# E-P-099-R3_0.net
KiCad netlist of a schematic drawn in EAGLE
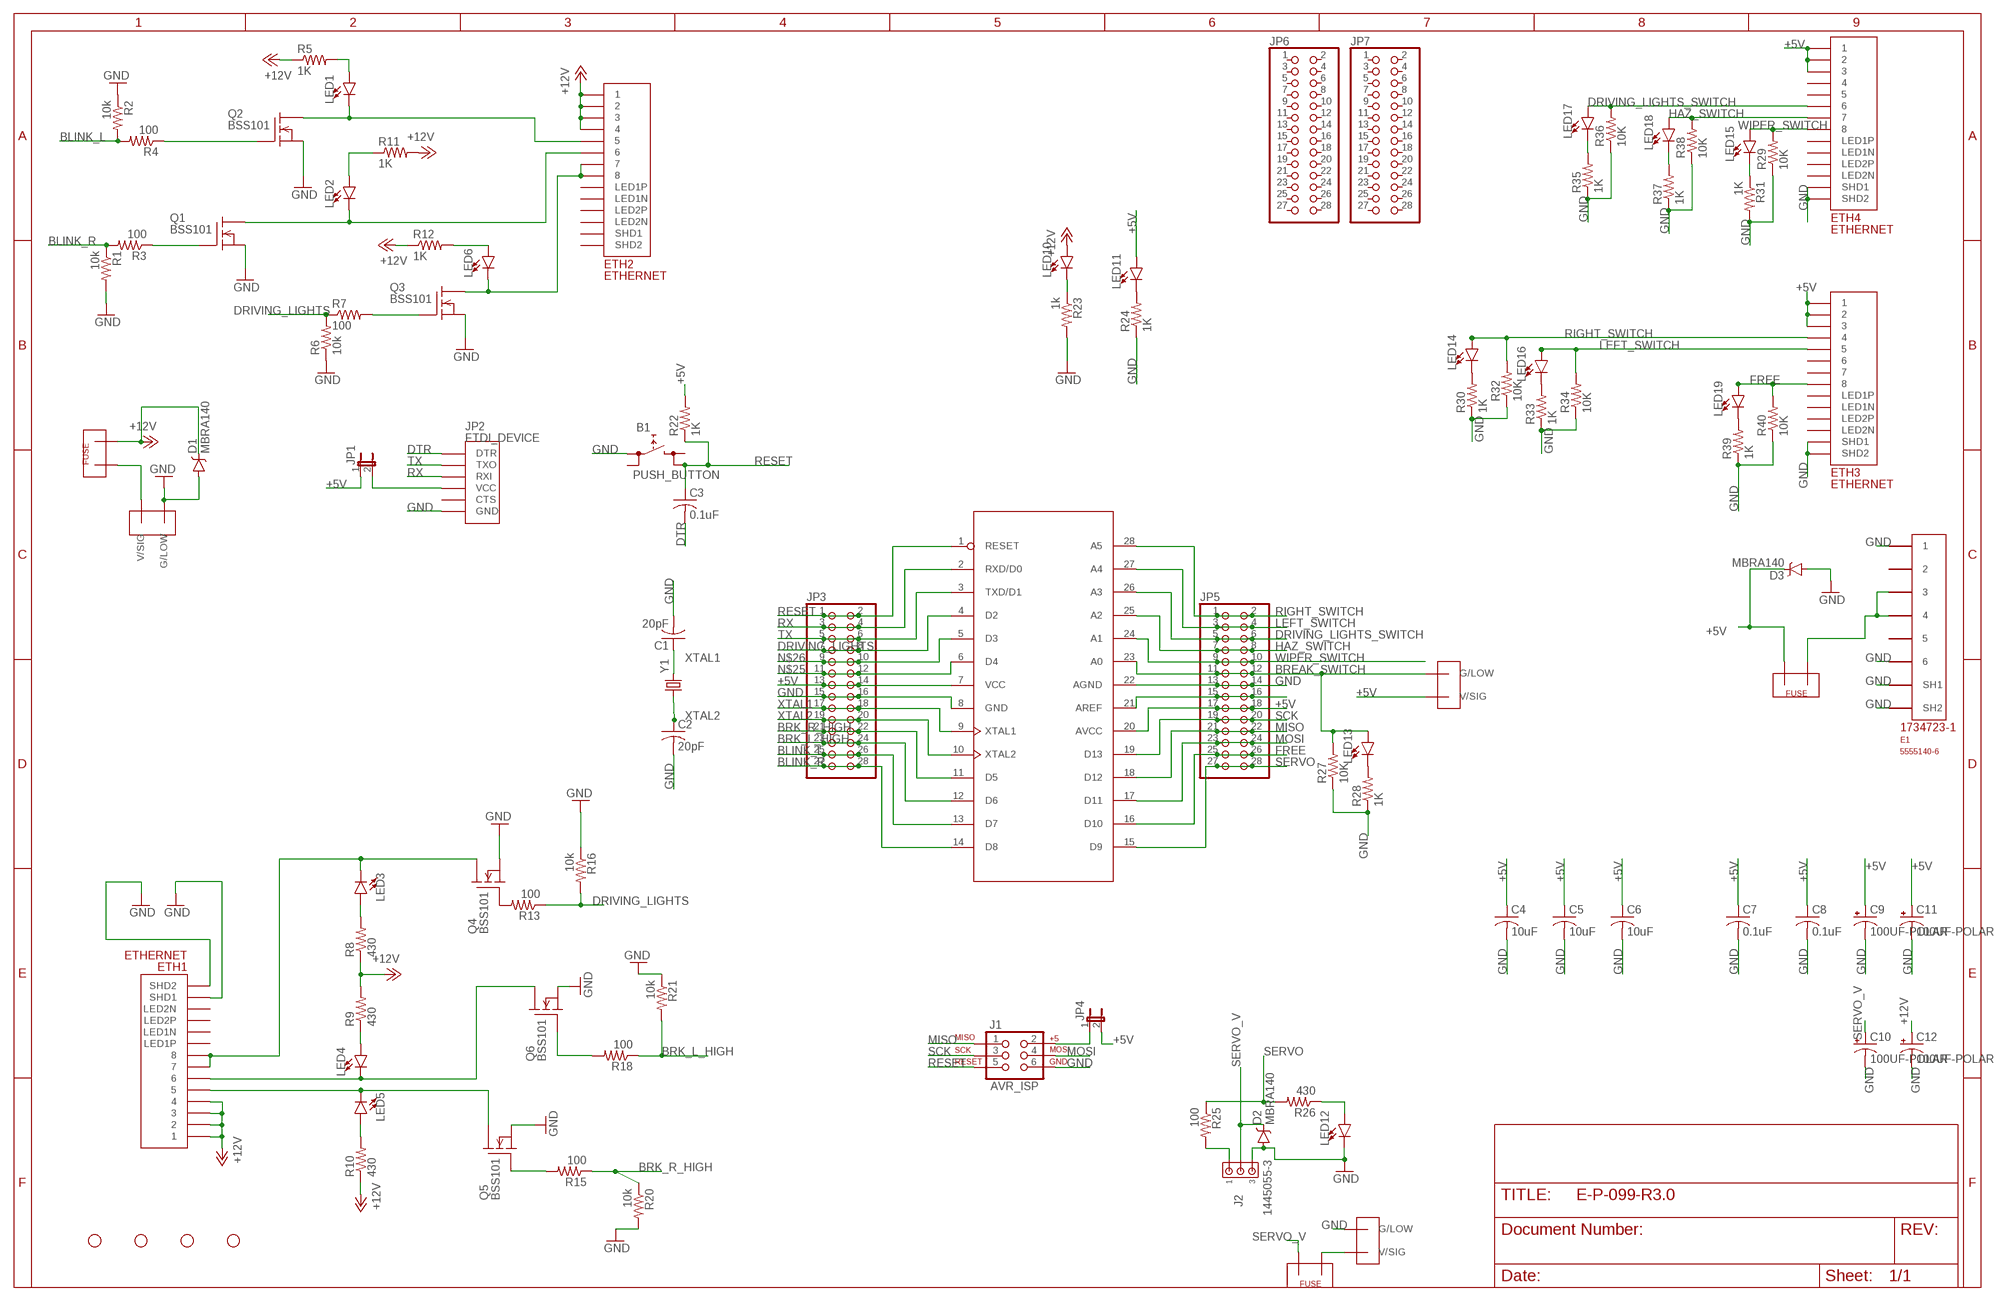
[diagram p0: schematic, sheet 1]

(export (version "E")
  (design (tool "Eeschema 10.0.6"))
  (components
    (comp (ref "AT1")
      (value "ATMEGA328")
      (footprint "eagle-import:DIP28-0.3IN")
      (libsource (lib "eagle-import") (part "ATMEGA328"))
    )
    (comp (ref "B1")
      (value "PUSH_BUTTON")
      (footprint "eagle-import:PUSHBUTTON")
      (libsource (lib "eagle-import") (part "PUSH_BUTTON"))
    )
    (comp (ref "C1")
      (value "20pF")
      (footprint "eagle-import:C0805")
      (libsource (lib "eagle-import") (part "C-USC0805"))
    )
    (comp (ref "C2")
      (value "20pF")
      (footprint "eagle-import:C0805")
      (libsource (lib "eagle-import") (part "C-USC0805"))
    )
    (comp (ref "C3")
      (value "0.1uF")
      (footprint "eagle-import:C0805")
      (libsource (lib "eagle-import") (part "C-USC0805"))
    )
    (comp (ref "C4")
      (value "10uF")
      (footprint "eagle-import:C0805")
      (libsource (lib "eagle-import") (part "C-USC0805"))
    )
    (comp (ref "C5")
      (value "10uF")
      (footprint "eagle-import:C0805")
      (libsource (lib "eagle-import") (part "C-USC0805"))
    )
    (comp (ref "C6")
      (value "10uF")
      (footprint "eagle-import:C0805")
      (libsource (lib "eagle-import") (part "C-USC0805"))
    )
    (comp (ref "C7")
      (value "0.1uF")
      (footprint "eagle-import:C0805")
      (libsource (lib "eagle-import") (part "C-USC0805"))
    )
    (comp (ref "C8")
      (value "0.1uF")
      (footprint "eagle-import:C0805")
      (libsource (lib "eagle-import") (part "C-USC0805"))
    )
    (comp (ref "C9")
      (value "100UF-POLAR")
      (footprint "eagle-import:EEU-FR1H101")
      (libsource (lib "eagle-import") (part "100UF-POLAR"))
    )
    (comp (ref "C10")
      (value "100UF-POLAR")
      (footprint "eagle-import:EEU-FR1H101")
      (libsource (lib "eagle-import") (part "100UF-POLAR"))
    )
    (comp (ref "C11")
      (value "100UF-POLAR")
      (footprint "eagle-import:EEU-FR1H101")
      (libsource (lib "eagle-import") (part "100UF-POLAR"))
    )
    (comp (ref "C12")
      (value "100UF-POLAR")
      (footprint "eagle-import:EEU-FR1H101")
      (libsource (lib "eagle-import") (part "100UF-POLAR"))
    )
    (comp (ref "D1")
      (value "MBRA140")
      (footprint "eagle-import:SMA-DIODE")
      (libsource (lib "eagle-import") (part "MBRA140"))
    )
    (comp (ref "D2")
      (value "MBRA140")
      (footprint "eagle-import:SMA-DIODE")
      (libsource (lib "eagle-import") (part "MBRA140"))
    )
    (comp (ref "D3")
      (value "MBRA140")
      (footprint "eagle-import:SMA-DIODE")
      (libsource (lib "eagle-import") (part "MBRA140"))
    )
    (comp (ref "E1")
      (value "5555140-6")
      (footprint "eagle-import:1734723-1_RJ11")
      (libsource (lib "eagle-import") (part "5555140-6"))
    )
    (comp (ref "ETH1")
      (value "ETHERNET")
      (footprint "eagle-import:A122645-ND")
      (libsource (lib "eagle-import") (part "ETHERNET"))
    )
    (comp (ref "ETH2")
      (value "ETHERNET")
      (footprint "eagle-import:A122645-ND")
      (libsource (lib "eagle-import") (part "ETHERNET"))
    )
    (comp (ref "ETH3")
      (value "ETHERNET")
      (footprint "eagle-import:A122645-ND")
      (libsource (lib "eagle-import") (part "ETHERNET"))
    )
    (comp (ref "ETH4")
      (value "ETHERNET")
      (footprint "eagle-import:A122645-ND")
      (libsource (lib "eagle-import") (part "ETHERNET"))
    )
    (comp (ref "F1")
      (value "FUSEMINI-BLADE")
      (footprint "eagle-import:MINI-BLADE-FUSE")
      (libsource (lib "eagle-import") (part "FUSEMINI-BLADE"))
    )
    (comp (ref "F2")
      (value "FUSEMINI-BLADE")
      (footprint "eagle-import:MINI-BLADE-FUSE")
      (libsource (lib "eagle-import") (part "FUSEMINI-BLADE"))
    )
    (comp (ref "F3")
      (value "FUSEMINI-BLADE")
      (footprint "eagle-import:MINI-BLADE-FUSE")
      (libsource (lib "eagle-import") (part "FUSEMINI-BLADE"))
    )
    (comp (ref "J1")
      (value "AVR_ISP")
      (footprint "eagle-import:2X3")
      (libsource (lib "eagle-import") (part "AVR_SPI_PRG_6PTH"))
    )
    (comp (ref "J2")
      (value "1445055-3")
      (footprint "eagle-import:1445055-3")
      (libsource (lib "eagle-import") (part "1445055-3"))
    )
    (comp (ref "JP1")
      (value "JP1E")
      (footprint "eagle-import:JP1")
      (libsource (lib "eagle-import") (part "JP1E"))
    )
    (comp (ref "JP2")
      (value "FTDI_DEVICE")
      (footprint "eagle-import:FTDI_DEVICE_SIDE")
      (libsource (lib "eagle-import") (part "FTDI_DEVICE"))
    )
    (comp (ref "JP3")
      (value "PINHD-2X14")
      (footprint "eagle-import:2X14")
      (libsource (lib "eagle-import") (part "PINHD-2X14"))
    )
    (comp (ref "JP4")
      (value "JP1E")
      (footprint "eagle-import:JP1")
      (libsource (lib "eagle-import") (part "JP1E"))
    )
    (comp (ref "JP5")
      (value "PINHD-2X14")
      (footprint "eagle-import:2X14")
      (libsource (lib "eagle-import") (part "PINHD-2X14"))
    )
    (comp (ref "JP6")
      (value "PINHD-2X14")
      (footprint "eagle-import:2X14")
      (libsource (lib "eagle-import") (part "PINHD-2X14"))
    )
    (comp (ref "JP7")
      (value "PINHD-2X14")
      (footprint "eagle-import:2X14")
      (libsource (lib "eagle-import") (part "PINHD-2X14"))
    )
    (comp (ref "LED1")
      (value "LED0603")
      (footprint "eagle-import:LED-0603")
      (libsource (lib "eagle-import") (part "LED0603"))
    )
    (comp (ref "LED2")
      (value "LED0603")
      (footprint "eagle-import:LED-0603")
      (libsource (lib "eagle-import") (part "LED0603"))
    )
    (comp (ref "LED3")
      (value "LED0603")
      (footprint "eagle-import:LED-0603")
      (libsource (lib "eagle-import") (part "LED0603"))
    )
    (comp (ref "LED4")
      (value "LED0603")
      (footprint "eagle-import:LED-0603")
      (libsource (lib "eagle-import") (part "LED0603"))
    )
    (comp (ref "LED5")
      (value "LED0603")
      (footprint "eagle-import:LED-0603")
      (libsource (lib "eagle-import") (part "LED0603"))
    )
    (comp (ref "LED6")
      (value "LED0603")
      (footprint "eagle-import:LED-0603")
      (libsource (lib "eagle-import") (part "LED0603"))
    )
    (comp (ref "LED10")
      (value "LED0603")
      (footprint "eagle-import:LED-0603")
      (libsource (lib "eagle-import") (part "LED0603"))
    )
    (comp (ref "LED11")
      (value "LED0603")
      (footprint "eagle-import:LED-0603")
      (libsource (lib "eagle-import") (part "LED0603"))
    )
    (comp (ref "LED12")
      (value "LED0603")
      (footprint "eagle-import:LED-0603")
      (libsource (lib "eagle-import") (part "LED0603"))
    )
    (comp (ref "LED13")
      (value "LED0603")
      (footprint "eagle-import:LED-0603")
      (libsource (lib "eagle-import") (part "LED0603"))
    )
    (comp (ref "LED14")
      (value "LED0603")
      (footprint "eagle-import:LED-0603")
      (libsource (lib "eagle-import") (part "LED0603"))
    )
    (comp (ref "LED15")
      (value "LED0603")
      (footprint "eagle-import:LED-0603")
      (libsource (lib "eagle-import") (part "LED0603"))
    )
    (comp (ref "LED16")
      (value "LED0603")
      (footprint "eagle-import:LED-0603")
      (libsource (lib "eagle-import") (part "LED0603"))
    )
    (comp (ref "LED17")
      (value "LED0603")
      (footprint "eagle-import:LED-0603")
      (libsource (lib "eagle-import") (part "LED0603"))
    )
    (comp (ref "LED18")
      (value "LED0603")
      (footprint "eagle-import:LED-0603")
      (libsource (lib "eagle-import") (part "LED0603"))
    )
    (comp (ref "LED19")
      (value "LED0603")
      (footprint "eagle-import:LED-0603")
      (libsource (lib "eagle-import") (part "LED0603"))
    )
    (comp (ref "Q1")
      (value "BSS101")
      (footprint "eagle-import:TO92")
      (libsource (lib "eagle-import") (part "BSS101"))
    )
    (comp (ref "Q2")
      (value "BSS101")
      (footprint "eagle-import:TO92")
      (libsource (lib "eagle-import") (part "BSS101"))
    )
    (comp (ref "Q3")
      (value "BSS101")
      (footprint "eagle-import:TO92")
      (libsource (lib "eagle-import") (part "BSS101"))
    )
    (comp (ref "Q4")
      (value "BSS101")
      (footprint "eagle-import:TO92")
      (libsource (lib "eagle-import") (part "BSS101"))
    )
    (comp (ref "Q5")
      (value "BSS101")
      (footprint "eagle-import:TO92")
      (libsource (lib "eagle-import") (part "BSS101"))
    )
    (comp (ref "Q6")
      (value "BSS101")
      (footprint "eagle-import:TO92")
      (libsource (lib "eagle-import") (part "BSS101"))
    )
    (comp (ref "R1")
      (value "10k")
      (footprint "eagle-import:0805")
      (libsource (lib "eagle-import") (part "RESISTOR0805-RES"))
    )
    (comp (ref "R2")
      (value "10k")
      (footprint "eagle-import:0805")
      (libsource (lib "eagle-import") (part "RESISTOR0805-RES"))
    )
    (comp (ref "R3")
      (value "100")
      (footprint "eagle-import:0805")
      (libsource (lib "eagle-import") (part "RESISTOR0805-RES"))
    )
    (comp (ref "R4")
      (value "100")
      (footprint "eagle-import:0805")
      (libsource (lib "eagle-import") (part "RESISTOR0805-RES"))
    )
    (comp (ref "R5")
      (value "1K")
      (footprint "eagle-import:0805")
      (libsource (lib "eagle-import") (part "RESISTOR0805-RES"))
    )
    (comp (ref "R6")
      (value "10k")
      (footprint "eagle-import:0805")
      (libsource (lib "eagle-import") (part "RESISTOR0805-RES"))
    )
    (comp (ref "R7")
      (value "100")
      (footprint "eagle-import:0805")
      (libsource (lib "eagle-import") (part "RESISTOR0805-RES"))
    )
    (comp (ref "R8")
      (value "430")
      (footprint "eagle-import:0805")
      (libsource (lib "eagle-import") (part "RESISTOR0805-RES"))
    )
    (comp (ref "R9")
      (value "430")
      (footprint "eagle-import:0805")
      (libsource (lib "eagle-import") (part "RESISTOR0805-RES"))
    )
    (comp (ref "R10")
      (value "430")
      (footprint "eagle-import:0805")
      (libsource (lib "eagle-import") (part "RESISTOR0805-RES"))
    )
    (comp (ref "R11")
      (value "1K")
      (footprint "eagle-import:0805")
      (libsource (lib "eagle-import") (part "RESISTOR0805-RES"))
    )
    (comp (ref "R12")
      (value "1K")
      (footprint "eagle-import:0805")
      (libsource (lib "eagle-import") (part "RESISTOR0805-RES"))
    )
    (comp (ref "R13")
      (value "100")
      (footprint "eagle-import:0805")
      (libsource (lib "eagle-import") (part "RESISTOR0805-RES"))
    )
    (comp (ref "R15")
      (value "100")
      (footprint "eagle-import:0805")
      (libsource (lib "eagle-import") (part "RESISTOR0805-RES"))
    )
    (comp (ref "R16")
      (value "10k")
      (footprint "eagle-import:0805")
      (libsource (lib "eagle-import") (part "RESISTOR0805-RES"))
    )
    (comp (ref "R18")
      (value "100")
      (footprint "eagle-import:0805")
      (libsource (lib "eagle-import") (part "RESISTOR0805-RES"))
    )
    (comp (ref "R20")
      (value "10k")
      (footprint "eagle-import:0805")
      (libsource (lib "eagle-import") (part "RESISTOR0805-RES"))
    )
    (comp (ref "R21")
      (value "10k")
      (footprint "eagle-import:0805")
      (libsource (lib "eagle-import") (part "RESISTOR0805-RES"))
    )
    (comp (ref "R22")
      (value "1K")
      (footprint "eagle-import:0805")
      (libsource (lib "eagle-import") (part "RESISTOR0805-RES"))
    )
    (comp (ref "R23")
      (value "1k")
      (footprint "eagle-import:0805")
      (libsource (lib "eagle-import") (part "RESISTOR0805-RES"))
    )
    (comp (ref "R24")
      (value "1K")
      (footprint "eagle-import:0805")
      (libsource (lib "eagle-import") (part "RESISTOR0805-RES"))
    )
    (comp (ref "R25")
      (value "100")
      (footprint "eagle-import:0805")
      (libsource (lib "eagle-import") (part "RESISTOR0805-RES"))
    )
    (comp (ref "R26")
      (value "430")
      (footprint "eagle-import:0805")
      (libsource (lib "eagle-import") (part "RESISTOR0805-RES"))
    )
    (comp (ref "R27")
      (value "10K")
      (footprint "eagle-import:R0805")
      (libsource (lib "eagle-import") (part "R-US_R0805"))
    )
    (comp (ref "R28")
      (value "1K")
      (footprint "eagle-import:0805")
      (libsource (lib "eagle-import") (part "RESISTOR0805-RES"))
    )
    (comp (ref "R29")
      (value "10K")
      (footprint "eagle-import:R0805")
      (libsource (lib "eagle-import") (part "R-US_R0805"))
    )
    (comp (ref "R30")
      (value "1K")
      (footprint "eagle-import:0805")
      (libsource (lib "eagle-import") (part "RESISTOR0805-RES"))
    )
    (comp (ref "R31")
      (value "1K")
      (footprint "eagle-import:0805")
      (libsource (lib "eagle-import") (part "RESISTOR0805-RES"))
    )
    (comp (ref "R32")
      (value "10K")
      (footprint "eagle-import:R0805")
      (libsource (lib "eagle-import") (part "R-US_R0805"))
    )
    (comp (ref "R33")
      (value "1K")
      (footprint "eagle-import:0805")
      (libsource (lib "eagle-import") (part "RESISTOR0805-RES"))
    )
    (comp (ref "R34")
      (value "10K")
      (footprint "eagle-import:R0805")
      (libsource (lib "eagle-import") (part "R-US_R0805"))
    )
    (comp (ref "R35")
      (value "1K")
      (footprint "eagle-import:0805")
      (libsource (lib "eagle-import") (part "RESISTOR0805-RES"))
    )
    (comp (ref "R36")
      (value "10K")
      (footprint "eagle-import:R0805")
      (libsource (lib "eagle-import") (part "R-US_R0805"))
    )
    (comp (ref "R37")
      (value "1K")
      (footprint "eagle-import:0805")
      (libsource (lib "eagle-import") (part "RESISTOR0805-RES"))
    )
    (comp (ref "R38")
      (value "10K")
      (footprint "eagle-import:R0805")
      (libsource (lib "eagle-import") (part "R-US_R0805"))
    )
    (comp (ref "R39")
      (value "1K")
      (footprint "eagle-import:0805")
      (libsource (lib "eagle-import") (part "RESISTOR0805-RES"))
    )
    (comp (ref "R40")
      (value "10K")
      (footprint "eagle-import:R0805")
      (libsource (lib "eagle-import") (part "R-US_R0805"))
    )
    (comp (ref "STANDOFF1")
      (value "STAND-OFF")
      (footprint "eagle-import:STAND-OFF")
      (libsource (lib "eagle-import") (part "STAND-OFF"))
    )
    (comp (ref "STANDOFF2")
      (value "STAND-OFF")
      (footprint "eagle-import:STAND-OFF")
      (libsource (lib "eagle-import") (part "STAND-OFF"))
    )
    (comp (ref "STANDOFF3")
      (value "STAND-OFF")
      (footprint "eagle-import:STAND-OFF")
      (libsource (lib "eagle-import") (part "STAND-OFF"))
    )
    (comp (ref "STANDOFF4")
      (value "STAND-OFF")
      (footprint "eagle-import:STAND-OFF")
      (libsource (lib "eagle-import") (part "STAND-OFF"))
    )
    (comp (ref "TE1")
      (value "TE770966")
      (footprint "eagle-import:2X1-MATE-N-LOCK")
      (libsource (lib "eagle-import") (part "TE770966"))
    )
    (comp (ref "TE2")
      (value "SERVO_PWR")
      (footprint "eagle-import:2X1-MATE-N-LOCK")
      (libsource (lib "eagle-import") (part "TE770966"))
    )
    (comp (ref "TE3")
      (value "TE770966")
      (footprint "eagle-import:2X1-MATE-N-LOCK")
      (libsource (lib "eagle-import") (part "TE770966"))
    )
    (comp (ref "Y1")
      (value "CRYSTALHC49US")
      (footprint "eagle-import:HC49US")
      (libsource (lib "eagle-import") (part "CRYSTALHC49US"))
    )
  )
  (nets
    (net (code "1") (name "+12V") (class "Default")
      (node (ref "C12") (pin "P") (pinfunction "+_P") (pintype "passive"))
      (node (ref "D1") (pin "C") (pinfunction "C_C") (pintype "passive"))
      (node (ref "ETH1") (pin "P$1") (pinfunction "1_P$1") (pintype "bidirectional"))
      (node (ref "ETH1") (pin "P$2") (pinfunction "2_P$2") (pintype "bidirectional"))
      (node (ref "ETH1") (pin "P$3") (pinfunction "3_P$3") (pintype "bidirectional"))
      (node (ref "ETH1") (pin "P$4") (pinfunction "4_P$4") (pintype "bidirectional"))
      (node (ref "ETH2") (pin "P$1") (pinfunction "1_P$1") (pintype "bidirectional"))
      (node (ref "ETH2") (pin "P$2") (pinfunction "2_P$2") (pintype "bidirectional"))
      (node (ref "ETH2") (pin "P$3") (pinfunction "3_P$3") (pintype "bidirectional"))
      (node (ref "ETH2") (pin "P$4") (pinfunction "4_P$4") (pintype "bidirectional"))
      (node (ref "F1") (pin "OUT") (pinfunction "OUT_OUT") (pintype "bidirectional"))
      (node (ref "LED10") (pin "A") (pinfunction "A_A") (pintype "passive"))
      (node (ref "R10") (pin "1") (pinfunction "1_1") (pintype "passive"))
      (node (ref "R11") (pin "2") (pinfunction "2_2") (pintype "passive"))
      (node (ref "R12") (pin "1") (pinfunction "1_1") (pintype "passive"))
      (node (ref "R5") (pin "1") (pinfunction "1_1") (pintype "passive"))
      (node (ref "R8") (pin "1") (pinfunction "1_1") (pintype "passive"))
      (node (ref "R9") (pin "2") (pinfunction "2_2") (pintype "passive"))
    )
    (net (code "2") (name "/+5V") (class "Default")
      (node (ref "AT1") (pin "20") (pinfunction "AVCC_20") (pintype "bidirectional"))
      (node (ref "AT1") (pin "7") (pinfunction "VCC_7") (pintype "bidirectional"))
      (node (ref "C11") (pin "P") (pinfunction "+_P") (pintype "passive"))
      (node (ref "C4") (pin "1") (pinfunction "1_1") (pintype "passive"))
      (node (ref "C5") (pin "1") (pinfunction "1_1") (pintype "passive"))
      (node (ref "C6") (pin "1") (pinfunction "1_1") (pintype "passive"))
      (node (ref "C7") (pin "1") (pinfunction "1_1") (pintype "passive"))
      (node (ref "C8") (pin "1") (pinfunction "1_1") (pintype "passive"))
      (node (ref "C9") (pin "P") (pinfunction "+_P") (pintype "passive"))
      (node (ref "D3") (pin "C") (pinfunction "C_C") (pintype "passive"))
      (node (ref "ETH3") (pin "P$1") (pinfunction "1_P$1") (pintype "bidirectional"))
      (node (ref "ETH3") (pin "P$2") (pinfunction "2_P$2") (pintype "bidirectional"))
      (node (ref "ETH3") (pin "P$3") (pinfunction "3_P$3") (pintype "bidirectional"))
      (node (ref "ETH4") (pin "P$1") (pinfunction "1_P$1") (pintype "bidirectional"))
      (node (ref "ETH4") (pin "P$2") (pinfunction "2_P$2") (pintype "bidirectional"))
      (node (ref "ETH4") (pin "P$3") (pinfunction "3_P$3") (pintype "bidirectional"))
      (node (ref "F3") (pin "OUT") (pinfunction "OUT_OUT") (pintype "bidirectional"))
      (node (ref "JP1") (pin "1") (pinfunction "1_1") (pintype "passive"))
      (node (ref "JP3") (pin "13") (pinfunction "13_13") (pintype "passive"))
      (node (ref "JP3") (pin "14") (pinfunction "14_14") (pintype "passive"))
      (node (ref "JP4") (pin "2") (pinfunction "2_2") (pintype "passive"))
      (node (ref "JP5") (pin "17") (pinfunction "17_17") (pintype "passive"))
      (node (ref "JP5") (pin "18") (pinfunction "18_18") (pintype "passive"))
      (node (ref "LED11") (pin "A") (pinfunction "A_A") (pintype "passive"))
      (node (ref "R22") (pin "2") (pinfunction "2_2") (pintype "passive"))
      (node (ref "TE3") (pin "CIRCUIT1") (pinfunction "V/SIG_CIRCUIT1") (pintype "bidirectional"))
    )
    (net (code "3") (name "/BLINK_L") (class "Default")
      (node (ref "AT1") (pin "13") (pinfunction "D7_13") (pintype "bidirectional"))
      (node (ref "JP3") (pin "25") (pinfunction "25_25") (pintype "passive"))
      (node (ref "JP3") (pin "26") (pinfunction "26_26") (pintype "passive"))
      (node (ref "R2") (pin "2") (pinfunction "2_2") (pintype "passive"))
      (node (ref "R4") (pin "2") (pinfunction "2_2") (pintype "passive"))
    )
    (net (code "4") (name "/BLINK_R") (class "Default")
      (node (ref "AT1") (pin "14") (pinfunction "D8_14") (pintype "bidirectional"))
      (node (ref "JP3") (pin "27") (pinfunction "27_27") (pintype "passive"))
      (node (ref "JP3") (pin "28") (pinfunction "28_28") (pintype "passive"))
      (node (ref "R1") (pin "1") (pinfunction "1_1") (pintype "passive"))
      (node (ref "R3") (pin "2") (pinfunction "2_2") (pintype "passive"))
    )
    (net (code "5") (name "/BREAK_SWITCH") (class "Default")
      (node (ref "AT1") (pin "23") (pinfunction "A0_23") (pintype "bidirectional"))
      (node (ref "JP5") (pin "11") (pinfunction "11_11") (pintype "passive"))
      (node (ref "JP5") (pin "12") (pinfunction "12_12") (pintype "passive"))
      (node (ref "LED13") (pin "A") (pinfunction "A_A") (pintype "passive"))
      (node (ref "R27") (pin "2") (pinfunction "2_2") (pintype "passive"))
      (node (ref "TE3") (pin "CIRCUIT2") (pinfunction "G/LOW_CIRCUIT2") (pintype "bidirectional"))
    )
    (net (code "6") (name "/BRK_L_HIGH") (class "Default")
      (node (ref "AT1") (pin "12") (pinfunction "D6_12") (pintype "bidirectional"))
      (node (ref "JP3") (pin "23") (pinfunction "23_23") (pintype "passive"))
      (node (ref "JP3") (pin "24") (pinfunction "24_24") (pintype "passive"))
      (node (ref "R18") (pin "1") (pinfunction "1_1") (pintype "passive"))
      (node (ref "R21") (pin "2") (pinfunction "2_2") (pintype "passive"))
    )
    (net (code "7") (name "/BRK_R_HIGH") (class "Default")
      (node (ref "AT1") (pin "11") (pinfunction "D5_11") (pintype "bidirectional"))
      (node (ref "JP3") (pin "21") (pinfunction "21_21") (pintype "passive"))
      (node (ref "JP3") (pin "22") (pinfunction "22_22") (pintype "passive"))
      (node (ref "R15") (pin "1") (pinfunction "1_1") (pintype "passive"))
      (node (ref "R20") (pin "1") (pinfunction "1_1") (pintype "passive"))
    )
    (net (code "8") (name "/DRIVING_LIGHTS") (class "Default")
      (node (ref "AT1") (pin "4") (pinfunction "D2_4") (pintype "bidirectional"))
      (node (ref "JP3") (pin "7") (pinfunction "7_7") (pintype "passive"))
      (node (ref "JP3") (pin "8") (pinfunction "8_8") (pintype "passive"))
      (node (ref "R13") (pin "1") (pinfunction "1_1") (pintype "passive"))
      (node (ref "R16") (pin "2") (pinfunction "2_2") (pintype "passive"))
      (node (ref "R6") (pin "2") (pinfunction "2_2") (pintype "passive"))
      (node (ref "R7") (pin "1") (pinfunction "1_1") (pintype "passive"))
    )
    (net (code "9") (name "/DRIVING_LIGHTS_SWITCH") (class "Default")
      (node (ref "AT1") (pin "26") (pinfunction "A3_26") (pintype "bidirectional"))
      (node (ref "ETH4") (pin "P$6") (pinfunction "6_P$6") (pintype "bidirectional"))
      (node (ref "JP5") (pin "5") (pinfunction "5_5") (pintype "passive"))
      (node (ref "JP5") (pin "6") (pinfunction "6_6") (pintype "passive"))
      (node (ref "LED17") (pin "A") (pinfunction "A_A") (pintype "passive"))
      (node (ref "R36") (pin "2") (pinfunction "2_2") (pintype "passive"))
    )
    (net (code "10") (name "/DTR") (class "Default")
      (node (ref "C3") (pin "2") (pinfunction "2_2") (pintype "passive"))
      (node (ref "JP2") (pin "P$1") (pinfunction "DTR_P$1") (pintype "bidirectional"))
    )
    (net (code "11") (name "/FREE") (class "Default")
      (node (ref "AT1") (pin "16") (pinfunction "D10_16") (pintype "bidirectional"))
      (node (ref "ETH3") (pin "P$8") (pinfunction "8_P$8") (pintype "bidirectional"))
      (node (ref "JP5") (pin "25") (pinfunction "25_25") (pintype "passive"))
      (node (ref "JP5") (pin "26") (pinfunction "26_26") (pintype "passive"))
      (node (ref "LED19") (pin "A") (pinfunction "A_A") (pintype "passive"))
      (node (ref "R40") (pin "2") (pinfunction "2_2") (pintype "passive"))
    )
    (net (code "12") (name "/HAZ_SWITCH") (class "Default")
      (node (ref "AT1") (pin "25") (pinfunction "A2_25") (pintype "bidirectional"))
      (node (ref "ETH4") (pin "P$7") (pinfunction "7_P$7") (pintype "bidirectional"))
      (node (ref "JP5") (pin "7") (pinfunction "7_7") (pintype "passive"))
      (node (ref "JP5") (pin "8") (pinfunction "8_8") (pintype "passive"))
      (node (ref "LED18") (pin "A") (pinfunction "A_A") (pintype "passive"))
      (node (ref "R38") (pin "2") (pinfunction "2_2") (pintype "passive"))
    )
    (net (code "13") (name "/LEFT_SWITCH") (class "Default")
      (node (ref "AT1") (pin "27") (pinfunction "A4_27") (pintype "bidirectional"))
      (node (ref "ETH3") (pin "P$5") (pinfunction "5_P$5") (pintype "bidirectional"))
      (node (ref "JP5") (pin "3") (pinfunction "3_3") (pintype "passive"))
      (node (ref "JP5") (pin "4") (pinfunction "4_4") (pintype "passive"))
      (node (ref "LED16") (pin "A") (pinfunction "A_A") (pintype "passive"))
      (node (ref "R34") (pin "2") (pinfunction "2_2") (pintype "passive"))
    )
    (net (code "14") (name "/MISO") (class "Default")
      (node (ref "AT1") (pin "18") (pinfunction "D12_18") (pintype "bidirectional"))
      (node (ref "J1") (pin "1") (pinfunction "1_1") (pintype "passive"))
      (node (ref "JP5") (pin "21") (pinfunction "21_21") (pintype "passive"))
      (node (ref "JP5") (pin "22") (pinfunction "22_22") (pintype "passive"))
    )
    (net (code "15") (name "/MOSI") (class "Default")
      (node (ref "AT1") (pin "17") (pinfunction "D11_17") (pintype "bidirectional"))
      (node (ref "J1") (pin "4") (pinfunction "4_4") (pintype "passive"))
      (node (ref "JP5") (pin "23") (pinfunction "23_23") (pintype "passive"))
      (node (ref "JP5") (pin "24") (pinfunction "24_24") (pintype "passive"))
    )
    (net (code "16") (name "/N$25") (class "Default")
      (node (ref "AT1") (pin "6") (pinfunction "D4_6") (pintype "bidirectional"))
      (node (ref "JP3") (pin "11") (pinfunction "11_11") (pintype "passive"))
      (node (ref "JP3") (pin "12") (pinfunction "12_12") (pintype "passive"))
    )
    (net (code "17") (name "/N$26") (class "Default")
      (node (ref "AT1") (pin "5") (pinfunction "D3_5") (pintype "bidirectional"))
      (node (ref "JP3") (pin "10") (pinfunction "10_10") (pintype "passive"))
      (node (ref "JP3") (pin "9") (pinfunction "9_9") (pintype "passive"))
    )
    (net (code "18") (name "/RESET") (class "Default")
      (node (ref "AT1") (pin "1") (pinfunction "RESET_1") (pintype "bidirectional"))
      (node (ref "B1") (pin "R2") (pinfunction "R_R2") (pintype "passive"))
      (node (ref "C3") (pin "1") (pinfunction "1_1") (pintype "passive"))
      (node (ref "J1") (pin "5") (pinfunction "5_5") (pintype "passive"))
      (node (ref "JP3") (pin "1") (pinfunction "1_1") (pintype "passive"))
      (node (ref "JP3") (pin "2") (pinfunction "2_2") (pintype "passive"))
      (node (ref "R22") (pin "1") (pinfunction "1_1") (pintype "passive"))
    )
    (net (code "19") (name "/RIGHT_SWITCH") (class "Default")
      (node (ref "AT1") (pin "28") (pinfunction "A5_28") (pintype "bidirectional"))
      (node (ref "ETH3") (pin "P$4") (pinfunction "4_P$4") (pintype "bidirectional"))
      (node (ref "JP5") (pin "1") (pinfunction "1_1") (pintype "passive"))
      (node (ref "JP5") (pin "2") (pinfunction "2_2") (pintype "passive"))
      (node (ref "LED14") (pin "A") (pinfunction "A_A") (pintype "passive"))
      (node (ref "R32") (pin "2") (pinfunction "2_2") (pintype "passive"))
    )
    (net (code "20") (name "/RX") (class "Default")
      (node (ref "AT1") (pin "2") (pinfunction "RXD/D0_2") (pintype "bidirectional"))
      (node (ref "JP2") (pin "P$3") (pinfunction "RXI_P$3") (pintype "bidirectional"))
      (node (ref "JP3") (pin "3") (pinfunction "3_3") (pintype "passive"))
      (node (ref "JP3") (pin "4") (pinfunction "4_4") (pintype "passive"))
    )
    (net (code "21") (name "/SCK") (class "Default")
      (node (ref "AT1") (pin "19") (pinfunction "D13_19") (pintype "bidirectional"))
      (node (ref "J1") (pin "3") (pinfunction "3_3") (pintype "passive"))
      (node (ref "JP5") (pin "19") (pinfunction "19_19") (pintype "passive"))
      (node (ref "JP5") (pin "20") (pinfunction "20_20") (pintype "passive"))
    )
    (net (code "22") (name "/SERVO") (class "Default")
      (node (ref "AT1") (pin "15") (pinfunction "D9_15") (pintype "bidirectional"))
      (node (ref "JP5") (pin "27") (pinfunction "27_27") (pintype "passive"))
      (node (ref "JP5") (pin "28") (pinfunction "28_28") (pintype "passive"))
      (node (ref "R25") (pin "1") (pinfunction "1_1") (pintype "passive"))
      (node (ref "R26") (pin "2") (pinfunction "2_2") (pintype "passive"))
    )
    (net (code "23") (name "/SERVO_V") (class "Default")
      (node (ref "C10") (pin "P") (pinfunction "+_P") (pintype "passive"))
      (node (ref "D2") (pin "C") (pinfunction "C_C") (pintype "passive"))
      (node (ref "F2") (pin "OUT") (pinfunction "OUT_OUT") (pintype "bidirectional"))
      (node (ref "J2") (pin "2") (pinfunction "2_2") (pintype "passive"))
    )
    (net (code "24") (name "/TX") (class "Default")
      (node (ref "AT1") (pin "3") (pinfunction "TXD/D1_3") (pintype "bidirectional"))
      (node (ref "JP2") (pin "P$2") (pinfunction "TXO_P$2") (pintype "bidirectional"))
      (node (ref "JP3") (pin "5") (pinfunction "5_5") (pintype "passive"))
      (node (ref "JP3") (pin "6") (pinfunction "6_6") (pintype "passive"))
    )
    (net (code "25") (name "/WIPER_SWITCH") (class "Default")
      (node (ref "AT1") (pin "24") (pinfunction "A1_24") (pintype "bidirectional"))
      (node (ref "ETH4") (pin "P$8") (pinfunction "8_P$8") (pintype "bidirectional"))
      (node (ref "JP5") (pin "10") (pinfunction "10_10") (pintype "passive"))
      (node (ref "JP5") (pin "9") (pinfunction "9_9") (pintype "passive"))
      (node (ref "LED15") (pin "A") (pinfunction "A_A") (pintype "passive"))
      (node (ref "R29") (pin "2") (pinfunction "2_2") (pintype "passive"))
    )
    (net (code "26") (name "/XTAL1") (class "Default")
      (node (ref "AT1") (pin "9") (pinfunction "XTAL1_9") (pintype "bidirectional"))
      (node (ref "C1") (pin "1") (pinfunction "1_1") (pintype "passive"))
      (node (ref "JP3") (pin "17") (pinfunction "17_17") (pintype "passive"))
      (node (ref "JP3") (pin "18") (pinfunction "18_18") (pintype "passive"))
      (node (ref "Y1") (pin "2") (pinfunction "2_2") (pintype "passive"))
    )
    (net (code "27") (name "/XTAL2") (class "Default")
      (node (ref "AT1") (pin "10") (pinfunction "XTAL2_10") (pintype "bidirectional"))
      (node (ref "C2") (pin "1") (pinfunction "1_1") (pintype "passive"))
      (node (ref "JP3") (pin "19") (pinfunction "19_19") (pintype "passive"))
      (node (ref "JP3") (pin "20") (pinfunction "20_20") (pintype "passive"))
      (node (ref "Y1") (pin "1") (pinfunction "1_1") (pintype "passive"))
    )
    (net (code "28") (name "GND") (class "Default")
      (node (ref "AT1") (pin "22") (pinfunction "AGND_22") (pintype "bidirectional"))
      (node (ref "AT1") (pin "8") (pinfunction "GND_8") (pintype "bidirectional"))
      (node (ref "B1") (pin "L1") (pinfunction "L_L1") (pintype "passive"))
      (node (ref "C1") (pin "2") (pinfunction "2_2") (pintype "passive"))
      (node (ref "C10") (pin "G") (pinfunction "-_G") (pintype "passive"))
      (node (ref "C11") (pin "G") (pinfunction "-_G") (pintype "passive"))
      (node (ref "C12") (pin "G") (pinfunction "-_G") (pintype "passive"))
      (node (ref "C2") (pin "2") (pinfunction "2_2") (pintype "passive"))
      (node (ref "C4") (pin "2") (pinfunction "2_2") (pintype "passive"))
      (node (ref "C5") (pin "2") (pinfunction "2_2") (pintype "passive"))
      (node (ref "C6") (pin "2") (pinfunction "2_2") (pintype "passive"))
      (node (ref "C7") (pin "2") (pinfunction "2_2") (pintype "passive"))
      (node (ref "C8") (pin "2") (pinfunction "2_2") (pintype "passive"))
      (node (ref "C9") (pin "G") (pinfunction "-_G") (pintype "passive"))
      (node (ref "D1") (pin "A") (pinfunction "A_A") (pintype "passive"))
      (node (ref "D2") (pin "A") (pinfunction "A_A") (pintype "passive"))
      (node (ref "D3") (pin "A") (pinfunction "A_A") (pintype "passive"))
      (node (ref "E1") (pin "1") (pinfunction "1_1") (pintype "bidirectional"))
      (node (ref "E1") (pin "6") (pinfunction "6_6") (pintype "bidirectional"))
      (node (ref "E1") (pin "SH1") (pinfunction "SH1_SH1") (pintype "bidirectional"))
      (node (ref "E1") (pin "SH2") (pinfunction "SH2_SH2") (pintype "bidirectional"))
      (node (ref "ETH1") (pin "P$13") (pinfunction "SHD1_P$13") (pintype "bidirectional"))
      (node (ref "ETH1") (pin "P$14") (pinfunction "SHD2_P$14") (pintype "bidirectional"))
      (node (ref "ETH3") (pin "P$13") (pinfunction "SHD1_P$13") (pintype "bidirectional"))
      (node (ref "ETH3") (pin "P$14") (pinfunction "SHD2_P$14") (pintype "bidirectional"))
      (node (ref "ETH4") (pin "P$13") (pinfunction "SHD1_P$13") (pintype "bidirectional"))
      (node (ref "ETH4") (pin "P$14") (pinfunction "SHD2_P$14") (pintype "bidirectional"))
      (node (ref "J1") (pin "6") (pinfunction "6_6") (pintype "passive"))
      (node (ref "J2") (pin "3") (pinfunction "3_3") (pintype "passive"))
      (node (ref "JP2") (pin "P$6") (pinfunction "GND_P$6") (pintype "bidirectional"))
      (node (ref "JP3") (pin "15") (pinfunction "15_15") (pintype "passive"))
      (node (ref "JP3") (pin "16") (pinfunction "16_16") (pintype "passive"))
      (node (ref "JP5") (pin "13") (pinfunction "13_13") (pintype "passive"))
      (node (ref "JP5") (pin "14") (pinfunction "14_14") (pintype "passive"))
      (node (ref "LED12") (pin "C") (pinfunction "C_C") (pintype "passive"))
      (node (ref "Q1") (pin "1") (pinfunction "S_1") (pintype "passive"))
      (node (ref "Q2") (pin "1") (pinfunction "S_1") (pintype "passive"))
      (node (ref "Q3") (pin "1") (pinfunction "S_1") (pintype "passive"))
      (node (ref "Q4") (pin "1") (pinfunction "S_1") (pintype "passive"))
      (node (ref "Q5") (pin "1") (pinfunction "S_1") (pintype "passive"))
      (node (ref "Q6") (pin "1") (pinfunction "S_1") (pintype "passive"))
      (node (ref "R1") (pin "2") (pinfunction "2_2") (pintype "passive"))
      (node (ref "R16") (pin "1") (pinfunction "1_1") (pintype "passive"))
      (node (ref "R2") (pin "1") (pinfunction "1_1") (pintype "passive"))
      (node (ref "R20") (pin "2") (pinfunction "2_2") (pintype "passive"))
      (node (ref "R21") (pin "1") (pinfunction "1_1") (pintype "passive"))
      (node (ref "R23") (pin "2") (pinfunction "2_2") (pintype "passive"))
      (node (ref "R24") (pin "1") (pinfunction "1_1") (pintype "passive"))
      (node (ref "R27") (pin "1") (pinfunction "1_1") (pintype "passive"))
      (node (ref "R28") (pin "1") (pinfunction "1_1") (pintype "passive"))
      (node (ref "R29") (pin "1") (pinfunction "1_1") (pintype "passive"))
      (node (ref "R30") (pin "1") (pinfunction "1_1") (pintype "passive"))
      (node (ref "R31") (pin "2") (pinfunction "2_2") (pintype "passive"))
      (node (ref "R32") (pin "1") (pinfunction "1_1") (pintype "passive"))
      (node (ref "R33") (pin "1") (pinfunction "1_1") (pintype "passive"))
      (node (ref "R34") (pin "1") (pinfunction "1_1") (pintype "passive"))
      (node (ref "R35") (pin "1") (pinfunction "1_1") (pintype "passive"))
      (node (ref "R36") (pin "1") (pinfunction "1_1") (pintype "passive"))
      (node (ref "R37") (pin "1") (pinfunction "1_1") (pintype "passive"))
      (node (ref "R38") (pin "1") (pinfunction "1_1") (pintype "passive"))
      (node (ref "R39") (pin "1") (pinfunction "1_1") (pintype "passive"))
      (node (ref "R40") (pin "1") (pinfunction "1_1") (pintype "passive"))
      (node (ref "R6") (pin "1") (pinfunction "1_1") (pintype "passive"))
      (node (ref "TE1") (pin "CIRCUIT2") (pinfunction "G/LOW_CIRCUIT2") (pintype "bidirectional"))
      (node (ref "TE2") (pin "CIRCUIT2") (pinfunction "G/LOW_CIRCUIT2") (pintype "bidirectional"))
    )
    (net (code "29") (name "Net-(AT1-AREF)") (class "Default")
      (node (ref "AT1") (pin "21") (pinfunction "AREF_21") (pintype "bidirectional"))
      (node (ref "JP5") (pin "15") (pinfunction "15_15") (pintype "passive"))
      (node (ref "JP5") (pin "16") (pinfunction "16_16") (pintype "passive"))
    )
    (net (code "30") (name "Net-(E1-Pad3)") (class "Default")
      (node (ref "E1") (pin "3") (pinfunction "3_3") (pintype "bidirectional"))
      (node (ref "E1") (pin "4") (pinfunction "4_4") (pintype "bidirectional"))
      (node (ref "F3") (pin "IN") (pinfunction "IN_IN") (pintype "bidirectional"))
    )
    (net (code "31") (name "Net-(ETH1-5)") (class "Default")
      (node (ref "ETH1") (pin "P$5") (pinfunction "5_P$5") (pintype "bidirectional"))
      (node (ref "LED5") (pin "C") (pinfunction "C_C") (pintype "passive"))
      (node (ref "Q5") (pin "3") (pinfunction "D_3") (pintype "passive"))
    )
    (net (code "32") (name "Net-(ETH1-6)") (class "Default")
      (node (ref "ETH1") (pin "P$6") (pinfunction "6_P$6") (pintype "bidirectional"))
      (node (ref "LED4") (pin "C") (pinfunction "C_C") (pintype "passive"))
      (node (ref "Q6") (pin "3") (pinfunction "D_3") (pintype "passive"))
    )
    (net (code "33") (name "Net-(ETH1-7)") (class "Default")
      (node (ref "ETH1") (pin "P$7") (pinfunction "7_P$7") (pintype "bidirectional"))
      (node (ref "ETH1") (pin "P$8") (pinfunction "8_P$8") (pintype "bidirectional"))
      (node (ref "LED3") (pin "C") (pinfunction "C_C") (pintype "passive"))
      (node (ref "Q4") (pin "3") (pinfunction "D_3") (pintype "passive"))
    )
    (net (code "34") (name "Net-(ETH2-5)") (class "Default")
      (node (ref "ETH2") (pin "P$5") (pinfunction "5_P$5") (pintype "bidirectional"))
      (node (ref "LED1") (pin "C") (pinfunction "C_C") (pintype "passive"))
      (node (ref "Q2") (pin "3") (pinfunction "D_3") (pintype "passive"))
    )
    (net (code "35") (name "Net-(ETH2-6)") (class "Default")
      (node (ref "ETH2") (pin "P$6") (pinfunction "6_P$6") (pintype "bidirectional"))
      (node (ref "LED2") (pin "C") (pinfunction "C_C") (pintype "passive"))
      (node (ref "Q1") (pin "3") (pinfunction "D_3") (pintype "passive"))
    )
    (net (code "36") (name "Net-(ETH2-7)") (class "Default")
      (node (ref "ETH2") (pin "P$7") (pinfunction "7_P$7") (pintype "bidirectional"))
      (node (ref "ETH2") (pin "P$8") (pinfunction "8_P$8") (pintype "bidirectional"))
      (node (ref "LED6") (pin "C") (pinfunction "C_C") (pintype "passive"))
      (node (ref "Q3") (pin "3") (pinfunction "D_3") (pintype "passive"))
    )
    (net (code "37") (name "Net-(J1-Pad2)") (class "Default")
      (node (ref "J1") (pin "2") (pinfunction "2_2") (pintype "passive"))
      (node (ref "JP4") (pin "1") (pinfunction "1_1") (pintype "passive"))
    )
    (net (code "38") (name "Net-(J2-Pad1)") (class "Default")
      (node (ref "J2") (pin "1") (pinfunction "1_1") (pintype "passive"))
      (node (ref "R25") (pin "2") (pinfunction "2_2") (pintype "passive"))
    )
    (net (code "39") (name "Net-(JP2-VCC)") (class "Default")
      (node (ref "JP1") (pin "2") (pinfunction "2_2") (pintype "passive"))
      (node (ref "JP2") (pin "P$4") (pinfunction "VCC_P$4") (pintype "bidirectional"))
    )
    (net (code "40") (name "Net-(LED1-PadA)") (class "Default")
      (node (ref "LED1") (pin "A") (pinfunction "A_A") (pintype "passive"))
      (node (ref "R5") (pin "2") (pinfunction "2_2") (pintype "passive"))
    )
    (net (code "41") (name "Net-(LED2-PadA)") (class "Default")
      (node (ref "LED2") (pin "A") (pinfunction "A_A") (pintype "passive"))
      (node (ref "R11") (pin "1") (pinfunction "1_1") (pintype "passive"))
    )
    (net (code "42") (name "Net-(LED3-PadA)") (class "Default")
      (node (ref "LED3") (pin "A") (pinfunction "A_A") (pintype "passive"))
      (node (ref "R8") (pin "2") (pinfunction "2_2") (pintype "passive"))
    )
    (net (code "43") (name "Net-(LED4-PadA)") (class "Default")
      (node (ref "LED4") (pin "A") (pinfunction "A_A") (pintype "passive"))
      (node (ref "R9") (pin "1") (pinfunction "1_1") (pintype "passive"))
    )
    (net (code "44") (name "Net-(LED5-PadA)") (class "Default")
      (node (ref "LED5") (pin "A") (pinfunction "A_A") (pintype "passive"))
      (node (ref "R10") (pin "2") (pinfunction "2_2") (pintype "passive"))
    )
    (net (code "45") (name "Net-(LED6-PadA)") (class "Default")
      (node (ref "LED6") (pin "A") (pinfunction "A_A") (pintype "passive"))
      (node (ref "R12") (pin "2") (pinfunction "2_2") (pintype "passive"))
    )
    (net (code "46") (name "Net-(LED10-PadC)") (class "Default")
      (node (ref "LED10") (pin "C") (pinfunction "C_C") (pintype "passive"))
      (node (ref "R23") (pin "1") (pinfunction "1_1") (pintype "passive"))
    )
    (net (code "47") (name "Net-(LED11-PadC)") (class "Default")
      (node (ref "LED11") (pin "C") (pinfunction "C_C") (pintype "passive"))
      (node (ref "R24") (pin "2") (pinfunction "2_2") (pintype "passive"))
    )
    (net (code "48") (name "Net-(LED12-PadA)") (class "Default")
      (node (ref "LED12") (pin "A") (pinfunction "A_A") (pintype "passive"))
      (node (ref "R26") (pin "1") (pinfunction "1_1") (pintype "passive"))
    )
    (net (code "49") (name "Net-(LED13-PadC)") (class "Default")
      (node (ref "LED13") (pin "C") (pinfunction "C_C") (pintype "passive"))
      (node (ref "R28") (pin "2") (pinfunction "2_2") (pintype "passive"))
    )
    (net (code "50") (name "Net-(LED14-PadC)") (class "Default")
      (node (ref "LED14") (pin "C") (pinfunction "C_C") (pintype "passive"))
      (node (ref "R30") (pin "2") (pinfunction "2_2") (pintype "passive"))
    )
    (net (code "51") (name "Net-(LED15-PadC)") (class "Default")
      (node (ref "LED15") (pin "C") (pinfunction "C_C") (pintype "passive"))
      (node (ref "R31") (pin "1") (pinfunction "1_1") (pintype "passive"))
    )
    (net (code "52") (name "Net-(LED16-PadC)") (class "Default")
      (node (ref "LED16") (pin "C") (pinfunction "C_C") (pintype "passive"))
      (node (ref "R33") (pin "2") (pinfunction "2_2") (pintype "passive"))
    )
    (net (code "53") (name "Net-(LED17-PadC)") (class "Default")
      (node (ref "LED17") (pin "C") (pinfunction "C_C") (pintype "passive"))
      (node (ref "R35") (pin "2") (pinfunction "2_2") (pintype "passive"))
    )
    (net (code "54") (name "Net-(LED18-PadC)") (class "Default")
      (node (ref "LED18") (pin "C") (pinfunction "C_C") (pintype "passive"))
      (node (ref "R37") (pin "2") (pinfunction "2_2") (pintype "passive"))
    )
    (net (code "55") (name "Net-(LED19-PadC)") (class "Default")
      (node (ref "LED19") (pin "C") (pinfunction "C_C") (pintype "passive"))
      (node (ref "R39") (pin "2") (pinfunction "2_2") (pintype "passive"))
    )
    (net (code "56") (name "Net-(Q1-G)") (class "Default")
      (node (ref "Q1") (pin "2") (pinfunction "G_2") (pintype "passive"))
      (node (ref "R3") (pin "1") (pinfunction "1_1") (pintype "passive"))
    )
    (net (code "57") (name "Net-(Q2-G)") (class "Default")
      (node (ref "Q2") (pin "2") (pinfunction "G_2") (pintype "passive"))
      (node (ref "R4") (pin "1") (pinfunction "1_1") (pintype "passive"))
    )
    (net (code "58") (name "Net-(Q3-G)") (class "Default")
      (node (ref "Q3") (pin "2") (pinfunction "G_2") (pintype "passive"))
      (node (ref "R7") (pin "2") (pinfunction "2_2") (pintype "passive"))
    )
    (net (code "59") (name "Net-(Q4-G)") (class "Default")
      (node (ref "Q4") (pin "2") (pinfunction "G_2") (pintype "passive"))
      (node (ref "R13") (pin "2") (pinfunction "2_2") (pintype "passive"))
    )
    (net (code "60") (name "Net-(Q5-G)") (class "Default")
      (node (ref "Q5") (pin "2") (pinfunction "G_2") (pintype "passive"))
      (node (ref "R15") (pin "2") (pinfunction "2_2") (pintype "passive"))
    )
    (net (code "61") (name "Net-(Q6-G)") (class "Default")
      (node (ref "Q6") (pin "2") (pinfunction "G_2") (pintype "passive"))
      (node (ref "R18") (pin "2") (pinfunction "2_2") (pintype "passive"))
    )
    (net (code "62") (name "Net-(TE1-V{slash}SIG)") (class "Default")
      (node (ref "F1") (pin "IN") (pinfunction "IN_IN") (pintype "bidirectional"))
      (node (ref "TE1") (pin "CIRCUIT1") (pinfunction "V/SIG_CIRCUIT1") (pintype "bidirectional"))
    )
    (net (code "63") (name "Net-(TE2-V{slash}SIG)") (class "Default")
      (node (ref "F2") (pin "IN") (pinfunction "IN_IN") (pintype "bidirectional"))
      (node (ref "TE2") (pin "CIRCUIT1") (pinfunction "V/SIG_CIRCUIT1") (pintype "bidirectional"))
    )
    (net (code "64") (name "unconnected-(B1-L-PadL2)") (class "Default")
      (node (ref "B1") (pin "L2") (pinfunction "L_L2") (pintype "passive"))
    )
    (net (code "65") (name "unconnected-(B1-R-PadR1)") (class "Default")
      (node (ref "B1") (pin "R1") (pinfunction "R_R1") (pintype "passive"))
    )
    (net (code "66") (name "unconnected-(E1-Pad2)") (class "Default")
      (node (ref "E1") (pin "2") (pinfunction "2_2") (pintype "bidirectional"))
    )
    (net (code "67") (name "unconnected-(E1-Pad5)") (class "Default")
      (node (ref "E1") (pin "5") (pinfunction "5_5") (pintype "bidirectional"))
    )
    (net (code "68") (name "unconnected-(ETH1-LED1N-PadP$9)") (class "Default")
      (node (ref "ETH1") (pin "P$9") (pinfunction "LED1N_P$9") (pintype "bidirectional"))
    )
    (net (code "69") (name "unconnected-(ETH1-LED1P-PadP$10)") (class "Default")
      (node (ref "ETH1") (pin "P$10") (pinfunction "LED1P_P$10") (pintype "bidirectional"))
    )
    (net (code "70") (name "unconnected-(ETH1-LED2N-PadP$11)") (class "Default")
      (node (ref "ETH1") (pin "P$11") (pinfunction "LED2N_P$11") (pintype "bidirectional"))
    )
    (net (code "71") (name "unconnected-(ETH1-LED2P-PadP$12)") (class "Default")
      (node (ref "ETH1") (pin "P$12") (pinfunction "LED2P_P$12") (pintype "bidirectional"))
    )
    (net (code "72") (name "unconnected-(ETH2-LED1N-PadP$9)") (class "Default")
      (node (ref "ETH2") (pin "P$9") (pinfunction "LED1N_P$9") (pintype "bidirectional"))
    )
    (net (code "73") (name "unconnected-(ETH2-LED1P-PadP$10)") (class "Default")
      (node (ref "ETH2") (pin "P$10") (pinfunction "LED1P_P$10") (pintype "bidirectional"))
    )
    (net (code "74") (name "unconnected-(ETH2-LED2N-PadP$11)") (class "Default")
      (node (ref "ETH2") (pin "P$11") (pinfunction "LED2N_P$11") (pintype "bidirectional"))
    )
    (net (code "75") (name "unconnected-(ETH2-LED2P-PadP$12)") (class "Default")
      (node (ref "ETH2") (pin "P$12") (pinfunction "LED2P_P$12") (pintype "bidirectional"))
    )
    (net (code "76") (name "unconnected-(ETH2-SHD1-PadP$13)") (class "Default")
      (node (ref "ETH2") (pin "P$13") (pinfunction "SHD1_P$13") (pintype "bidirectional"))
    )
    (net (code "77") (name "unconnected-(ETH2-SHD2-PadP$14)") (class "Default")
      (node (ref "ETH2") (pin "P$14") (pinfunction "SHD2_P$14") (pintype "bidirectional"))
    )
    (net (code "78") (name "unconnected-(ETH3-6-PadP$6)") (class "Default")
      (node (ref "ETH3") (pin "P$6") (pinfunction "6_P$6") (pintype "bidirectional"))
    )
    (net (code "79") (name "unconnected-(ETH3-7-PadP$7)") (class "Default")
      (node (ref "ETH3") (pin "P$7") (pinfunction "7_P$7") (pintype "bidirectional"))
    )
    (net (code "80") (name "unconnected-(ETH3-LED1N-PadP$9)") (class "Default")
      (node (ref "ETH3") (pin "P$9") (pinfunction "LED1N_P$9") (pintype "bidirectional"))
    )
    (net (code "81") (name "unconnected-(ETH3-LED1P-PadP$10)") (class "Default")
      (node (ref "ETH3") (pin "P$10") (pinfunction "LED1P_P$10") (pintype "bidirectional"))
    )
    (net (code "82") (name "unconnected-(ETH3-LED2N-PadP$11)") (class "Default")
      (node (ref "ETH3") (pin "P$11") (pinfunction "LED2N_P$11") (pintype "bidirectional"))
    )
    (net (code "83") (name "unconnected-(ETH3-LED2P-PadP$12)") (class "Default")
      (node (ref "ETH3") (pin "P$12") (pinfunction "LED2P_P$12") (pintype "bidirectional"))
    )
    (net (code "84") (name "unconnected-(ETH4-4-PadP$4)") (class "Default")
      (node (ref "ETH4") (pin "P$4") (pinfunction "4_P$4") (pintype "bidirectional"))
    )
    (net (code "85") (name "unconnected-(ETH4-5-PadP$5)") (class "Default")
      (node (ref "ETH4") (pin "P$5") (pinfunction "5_P$5") (pintype "bidirectional"))
    )
    (net (code "86") (name "unconnected-(ETH4-LED1N-PadP$9)") (class "Default")
      (node (ref "ETH4") (pin "P$9") (pinfunction "LED1N_P$9") (pintype "bidirectional"))
    )
    (net (code "87") (name "unconnected-(ETH4-LED1P-PadP$10)") (class "Default")
      (node (ref "ETH4") (pin "P$10") (pinfunction "LED1P_P$10") (pintype "bidirectional"))
    )
    (net (code "88") (name "unconnected-(ETH4-LED2N-PadP$11)") (class "Default")
      (node (ref "ETH4") (pin "P$11") (pinfunction "LED2N_P$11") (pintype "bidirectional"))
    )
    (net (code "89") (name "unconnected-(ETH4-LED2P-PadP$12)") (class "Default")
      (node (ref "ETH4") (pin "P$12") (pinfunction "LED2P_P$12") (pintype "bidirectional"))
    )
    (net (code "90") (name "unconnected-(JP2-CTS-PadP$5)") (class "Default")
      (node (ref "JP2") (pin "P$5") (pinfunction "CTS_P$5") (pintype "bidirectional"))
    )
    (net (code "91") (name "unconnected-(JP6-Pad1)") (class "Default")
      (node (ref "JP6") (pin "1") (pinfunction "1_1") (pintype "passive"))
    )
    (net (code "92") (name "unconnected-(JP6-Pad2)") (class "Default")
      (node (ref "JP6") (pin "2") (pinfunction "2_2") (pintype "passive"))
    )
    (net (code "93") (name "unconnected-(JP6-Pad3)") (class "Default")
      (node (ref "JP6") (pin "3") (pinfunction "3_3") (pintype "passive"))
    )
    (net (code "94") (name "unconnected-(JP6-Pad4)") (class "Default")
      (node (ref "JP6") (pin "4") (pinfunction "4_4") (pintype "passive"))
    )
    (net (code "95") (name "unconnected-(JP6-Pad5)") (class "Default")
      (node (ref "JP6") (pin "5") (pinfunction "5_5") (pintype "passive"))
    )
    (net (code "96") (name "unconnected-(JP6-Pad6)") (class "Default")
      (node (ref "JP6") (pin "6") (pinfunction "6_6") (pintype "passive"))
    )
    (net (code "97") (name "unconnected-(JP6-Pad7)") (class "Default")
      (node (ref "JP6") (pin "7") (pinfunction "7_7") (pintype "passive"))
    )
    (net (code "98") (name "unconnected-(JP6-Pad8)") (class "Default")
      (node (ref "JP6") (pin "8") (pinfunction "8_8") (pintype "passive"))
    )
    (net (code "99") (name "unconnected-(JP6-Pad9)") (class "Default")
      (node (ref "JP6") (pin "9") (pinfunction "9_9") (pintype "passive"))
    )
    (net (code "100") (name "unconnected-(JP6-Pad10)") (class "Default")
      (node (ref "JP6") (pin "10") (pinfunction "10_10") (pintype "passive"))
    )
    (net (code "101") (name "unconnected-(JP6-Pad11)") (class "Default")
      (node (ref "JP6") (pin "11") (pinfunction "11_11") (pintype "passive"))
    )
    (net (code "102") (name "unconnected-(JP6-Pad12)") (class "Default")
      (node (ref "JP6") (pin "12") (pinfunction "12_12") (pintype "passive"))
    )
    (net (code "103") (name "unconnected-(JP6-Pad13)") (class "Default")
      (node (ref "JP6") (pin "13") (pinfunction "13_13") (pintype "passive"))
    )
    (net (code "104") (name "unconnected-(JP6-Pad14)") (class "Default")
      (node (ref "JP6") (pin "14") (pinfunction "14_14") (pintype "passive"))
    )
    (net (code "105") (name "unconnected-(JP6-Pad15)") (class "Default")
      (node (ref "JP6") (pin "15") (pinfunction "15_15") (pintype "passive"))
    )
    (net (code "106") (name "unconnected-(JP6-Pad16)") (class "Default")
      (node (ref "JP6") (pin "16") (pinfunction "16_16") (pintype "passive"))
    )
    (net (code "107") (name "unconnected-(JP6-Pad17)") (class "Default")
      (node (ref "JP6") (pin "17") (pinfunction "17_17") (pintype "passive"))
    )
    (net (code "108") (name "unconnected-(JP6-Pad18)") (class "Default")
      (node (ref "JP6") (pin "18") (pinfunction "18_18") (pintype "passive"))
    )
    (net (code "109") (name "unconnected-(JP6-Pad19)") (class "Default")
      (node (ref "JP6") (pin "19") (pinfunction "19_19") (pintype "passive"))
    )
    (net (code "110") (name "unconnected-(JP6-Pad20)") (class "Default")
      (node (ref "JP6") (pin "20") (pinfunction "20_20") (pintype "passive"))
    )
    (net (code "111") (name "unconnected-(JP6-Pad21)") (class "Default")
      (node (ref "JP6") (pin "21") (pinfunction "21_21") (pintype "passive"))
    )
    (net (code "112") (name "unconnected-(JP6-Pad22)") (class "Default")
      (node (ref "JP6") (pin "22") (pinfunction "22_22") (pintype "passive"))
    )
    (net (code "113") (name "unconnected-(JP6-Pad23)") (class "Default")
      (node (ref "JP6") (pin "23") (pinfunction "23_23") (pintype "passive"))
    )
    (net (code "114") (name "unconnected-(JP6-Pad24)") (class "Default")
      (node (ref "JP6") (pin "24") (pinfunction "24_24") (pintype "passive"))
    )
    (net (code "115") (name "unconnected-(JP6-Pad25)") (class "Default")
      (node (ref "JP6") (pin "25") (pinfunction "25_25") (pintype "passive"))
    )
    (net (code "116") (name "unconnected-(JP6-Pad26)") (class "Default")
      (node (ref "JP6") (pin "26") (pinfunction "26_26") (pintype "passive"))
    )
    (net (code "117") (name "unconnected-(JP6-Pad27)") (class "Default")
      (node (ref "JP6") (pin "27") (pinfunction "27_27") (pintype "passive"))
    )
    (net (code "118") (name "unconnected-(JP6-Pad28)") (class "Default")
      (node (ref "JP6") (pin "28") (pinfunction "28_28") (pintype "passive"))
    )
    (net (code "119") (name "unconnected-(JP7-Pad1)") (class "Default")
      (node (ref "JP7") (pin "1") (pinfunction "1_1") (pintype "passive"))
    )
    (net (code "120") (name "unconnected-(JP7-Pad2)") (class "Default")
      (node (ref "JP7") (pin "2") (pinfunction "2_2") (pintype "passive"))
    )
    (net (code "121") (name "unconnected-(JP7-Pad3)") (class "Default")
      (node (ref "JP7") (pin "3") (pinfunction "3_3") (pintype "passive"))
    )
    (net (code "122") (name "unconnected-(JP7-Pad4)") (class "Default")
      (node (ref "JP7") (pin "4") (pinfunction "4_4") (pintype "passive"))
    )
    (net (code "123") (name "unconnected-(JP7-Pad5)") (class "Default")
      (node (ref "JP7") (pin "5") (pinfunction "5_5") (pintype "passive"))
    )
    (net (code "124") (name "unconnected-(JP7-Pad6)") (class "Default")
      (node (ref "JP7") (pin "6") (pinfunction "6_6") (pintype "passive"))
    )
    (net (code "125") (name "unconnected-(JP7-Pad7)") (class "Default")
      (node (ref "JP7") (pin "7") (pinfunction "7_7") (pintype "passive"))
    )
    (net (code "126") (name "unconnected-(JP7-Pad8)") (class "Default")
      (node (ref "JP7") (pin "8") (pinfunction "8_8") (pintype "passive"))
    )
    (net (code "127") (name "unconnected-(JP7-Pad9)") (class "Default")
      (node (ref "JP7") (pin "9") (pinfunction "9_9") (pintype "passive"))
    )
    (net (code "128") (name "unconnected-(JP7-Pad10)") (class "Default")
      (node (ref "JP7") (pin "10") (pinfunction "10_10") (pintype "passive"))
    )
    (net (code "129") (name "unconnected-(JP7-Pad11)") (class "Default")
      (node (ref "JP7") (pin "11") (pinfunction "11_11") (pintype "passive"))
    )
    (net (code "130") (name "unconnected-(JP7-Pad12)") (class "Default")
      (node (ref "JP7") (pin "12") (pinfunction "12_12") (pintype "passive"))
    )
    (net (code "131") (name "unconnected-(JP7-Pad13)") (class "Default")
      (node (ref "JP7") (pin "13") (pinfunction "13_13") (pintype "passive"))
    )
    (net (code "132") (name "unconnected-(JP7-Pad14)") (class "Default")
      (node (ref "JP7") (pin "14") (pinfunction "14_14") (pintype "passive"))
    )
    (net (code "133") (name "unconnected-(JP7-Pad15)") (class "Default")
      (node (ref "JP7") (pin "15") (pinfunction "15_15") (pintype "passive"))
    )
    (net (code "134") (name "unconnected-(JP7-Pad16)") (class "Default")
      (node (ref "JP7") (pin "16") (pinfunction "16_16") (pintype "passive"))
    )
    (net (code "135") (name "unconnected-(JP7-Pad17)") (class "Default")
      (node (ref "JP7") (pin "17") (pinfunction "17_17") (pintype "passive"))
    )
    (net (code "136") (name "unconnected-(JP7-Pad18)") (class "Default")
      (node (ref "JP7") (pin "18") (pinfunction "18_18") (pintype "passive"))
    )
    (net (code "137") (name "unconnected-(JP7-Pad19)") (class "Default")
      (node (ref "JP7") (pin "19") (pinfunction "19_19") (pintype "passive"))
    )
    (net (code "138") (name "unconnected-(JP7-Pad20)") (class "Default")
      (node (ref "JP7") (pin "20") (pinfunction "20_20") (pintype "passive"))
    )
    (net (code "139") (name "unconnected-(JP7-Pad21)") (class "Default")
      (node (ref "JP7") (pin "21") (pinfunction "21_21") (pintype "passive"))
    )
    (net (code "140") (name "unconnected-(JP7-Pad22)") (class "Default")
      (node (ref "JP7") (pin "22") (pinfunction "22_22") (pintype "passive"))
    )
    (net (code "141") (name "unconnected-(JP7-Pad23)") (class "Default")
      (node (ref "JP7") (pin "23") (pinfunction "23_23") (pintype "passive"))
    )
    (net (code "142") (name "unconnected-(JP7-Pad24)") (class "Default")
      (node (ref "JP7") (pin "24") (pinfunction "24_24") (pintype "passive"))
    )
    (net (code "143") (name "unconnected-(JP7-Pad25)") (class "Default")
      (node (ref "JP7") (pin "25") (pinfunction "25_25") (pintype "passive"))
    )
    (net (code "144") (name "unconnected-(JP7-Pad26)") (class "Default")
      (node (ref "JP7") (pin "26") (pinfunction "26_26") (pintype "passive"))
    )
    (net (code "145") (name "unconnected-(JP7-Pad27)") (class "Default")
      (node (ref "JP7") (pin "27") (pinfunction "27_27") (pintype "passive"))
    )
    (net (code "146") (name "unconnected-(JP7-Pad28)") (class "Default")
      (node (ref "JP7") (pin "28") (pinfunction "28_28") (pintype "passive"))
    )
  )
)
